# 6pil-2motor-1back.net
KiCad netlist of a schematic drawn in EAGLE
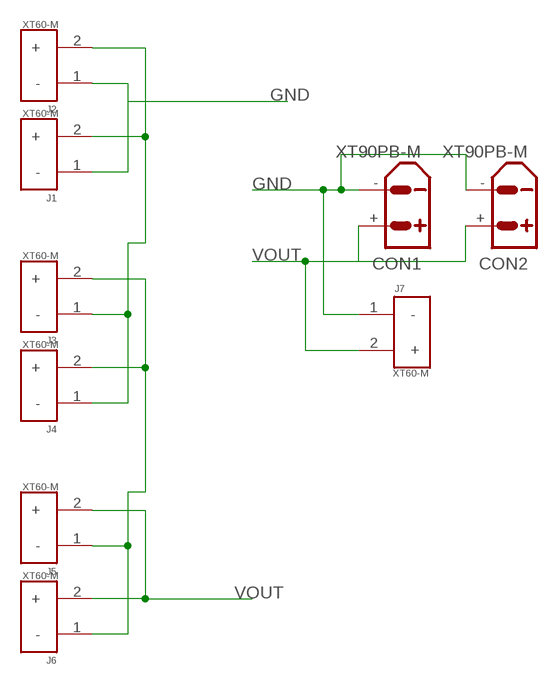
[diagram p0: schematic, sheet 1]

(export (version "E")
  (design (tool "Eeschema 10.0.6"))
  (components
    (comp (ref "CON1")
      (value "XT90PB-M")
      (footprint "eagle-import:XT90PB-M")
      (libsource (lib "eagle-import") (part "XT90PB-M"))
    )
    (comp (ref "CON2")
      (value "XT90PB-M")
      (footprint "eagle-import:XT90PB-M")
      (libsource (lib "eagle-import") (part "XT90PB-M"))
    )
    (comp (ref "J1")
      (value "XT60-M")
      (footprint "eagle-import:AMASS_XT60-M")
      (fields (field (name "MF") "AMASS"))
      (libsource (lib "eagle-import") (part "XT60-M"))
    )
    (comp (ref "J2")
      (value "XT60-M")
      (footprint "eagle-import:AMASS_XT60-M")
      (fields (field (name "MF") "AMASS"))
      (libsource (lib "eagle-import") (part "XT60-M"))
    )
    (comp (ref "J3")
      (value "XT60-M")
      (footprint "eagle-import:AMASS_XT60-M")
      (fields (field (name "MF") "AMASS"))
      (libsource (lib "eagle-import") (part "XT60-M"))
    )
    (comp (ref "J4")
      (value "XT60-M")
      (footprint "eagle-import:AMASS_XT60-M")
      (fields (field (name "MF") "AMASS"))
      (libsource (lib "eagle-import") (part "XT60-M"))
    )
    (comp (ref "J5")
      (value "XT60-M")
      (footprint "eagle-import:AMASS_XT60-M")
      (fields (field (name "MF") "AMASS"))
      (libsource (lib "eagle-import") (part "XT60-M"))
    )
    (comp (ref "J6")
      (value "XT60-M")
      (footprint "eagle-import:AMASS_XT60-M")
      (fields (field (name "MF") "AMASS"))
      (libsource (lib "eagle-import") (part "XT60-M"))
    )
    (comp (ref "J7")
      (value "XT60-M")
      (footprint "eagle-import:AMASS_XT60-M")
      (fields (field (name "MF") "AMASS"))
      (libsource (lib "eagle-import") (part "XT60-M"))
    )
  )
  (nets
    (net (code "1") (name "/GND") (class "Default")
      (node (ref "CON1") (pin "-") (pinfunction "-_-") (pintype "power_in"))
      (node (ref "CON2") (pin "-") (pinfunction "-_-") (pintype "power_in"))
      (node (ref "J1") (pin "1") (pinfunction "-_1") (pintype "passive"))
      (node (ref "J2") (pin "1") (pinfunction "-_1") (pintype "passive"))
      (node (ref "J7") (pin "1") (pinfunction "-_1") (pintype "passive"))
    )
    (net (code "2") (name "/VOUT") (class "Default")
      (node (ref "CON1") (pin "+") (pinfunction "+_+") (pintype "power_in"))
      (node (ref "CON2") (pin "+") (pinfunction "+_+") (pintype "power_in"))
      (node (ref "J5") (pin "2") (pinfunction "+_2") (pintype "passive"))
      (node (ref "J6") (pin "2") (pinfunction "+_2") (pintype "passive"))
      (node (ref "J7") (pin "2") (pinfunction "+_2") (pintype "passive"))
    )
    (net (code "3") (name "Net-(J1-+)") (class "Default")
      (node (ref "J1") (pin "2") (pinfunction "+_2") (pintype "passive"))
      (node (ref "J2") (pin "2") (pinfunction "+_2") (pintype "passive"))
      (node (ref "J3") (pin "1") (pinfunction "-_1") (pintype "passive"))
      (node (ref "J4") (pin "1") (pinfunction "-_1") (pintype "passive"))
    )
    (net (code "4") (name "Net-(J3-+)") (class "Default")
      (node (ref "J3") (pin "2") (pinfunction "+_2") (pintype "passive"))
      (node (ref "J4") (pin "2") (pinfunction "+_2") (pintype "passive"))
      (node (ref "J5") (pin "1") (pinfunction "-_1") (pintype "passive"))
      (node (ref "J6") (pin "1") (pinfunction "-_1") (pintype "passive"))
    )
  )
)
